# Simulation.net
KiCad netlist of a schematic drawn in EasyEDA
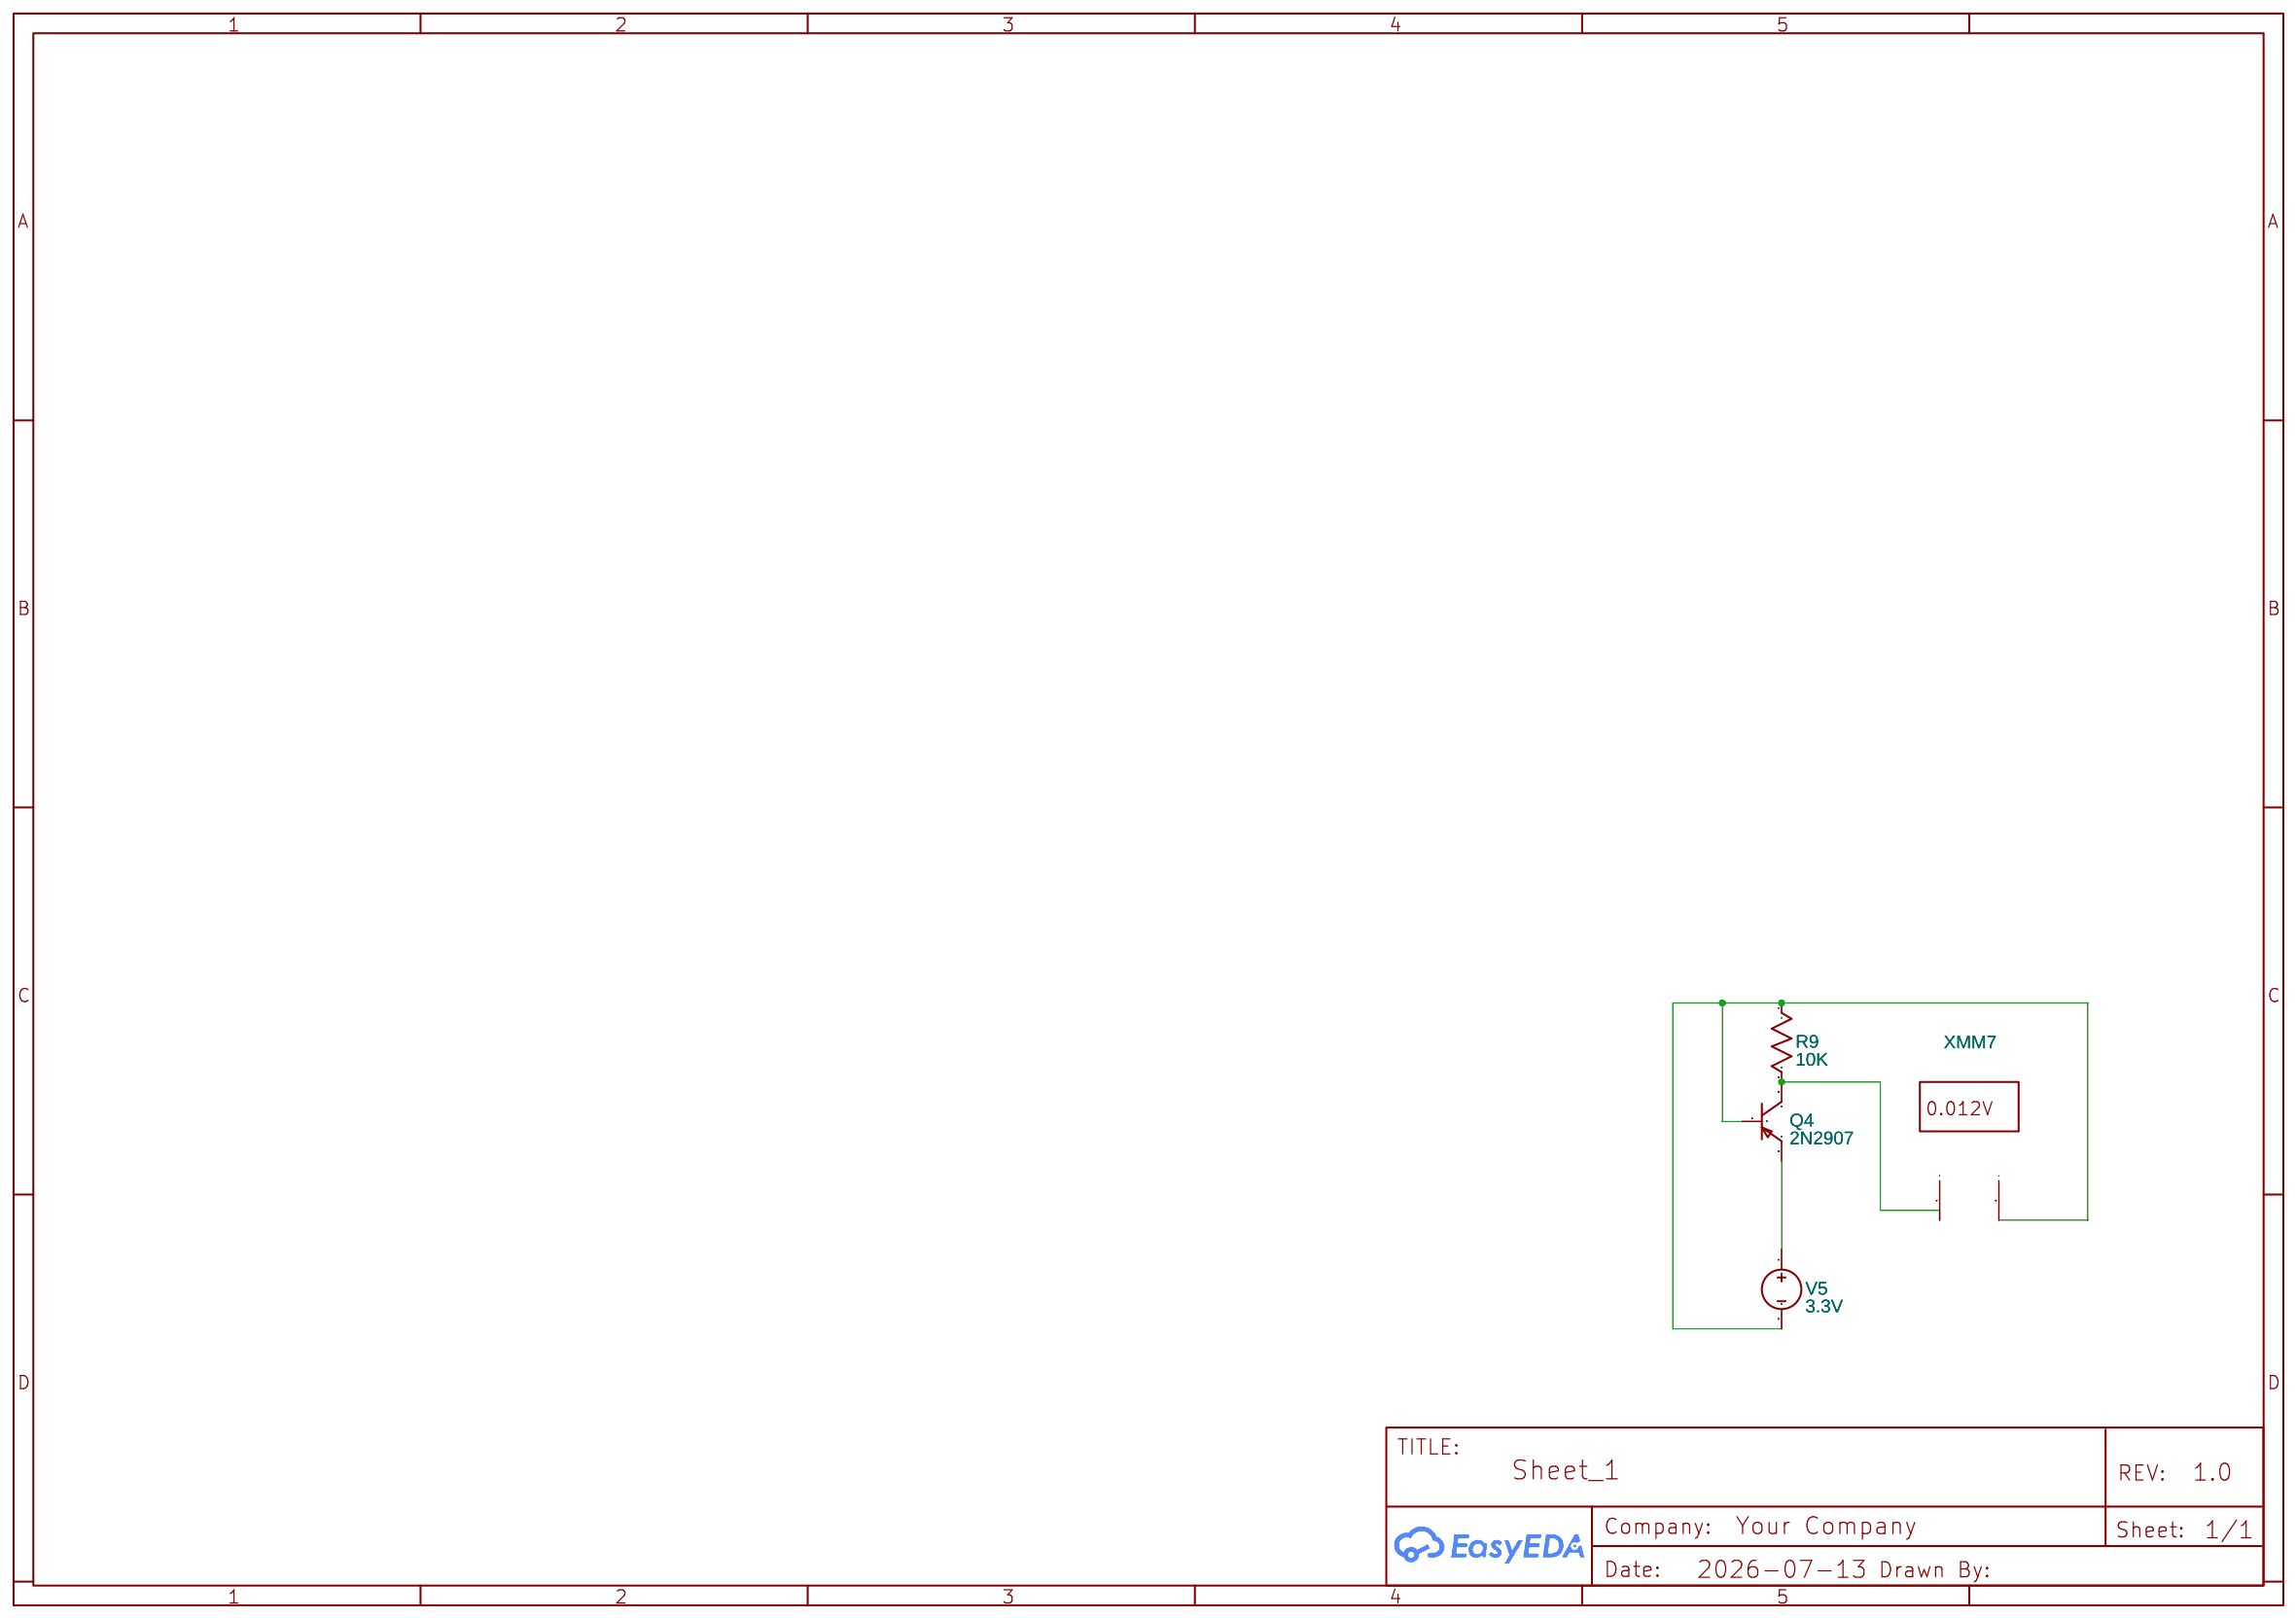
[diagram p0: schematic sheet]

(export (version "E")
  (design (tool "Eeschema 10.0.6"))
  (components
    (comp (ref "Q4") (value "2N2907") (libsource (lib "") (part "2N2907")))
    (comp (ref "R9") (value "10K") (libsource (lib "") (part "R_0603_US")))
    (comp (ref "V5") (value "3.3V") (libsource (lib "") (part "VDC")))
    (comp (ref "XMM7") (value "Multimeter") (libsource (lib "") (part "MULTIMETER")))
  )
  (nets
    (net (code "1") (name "Net-(Q4-B)") (class "Default")
      (node (ref "Q4") (pin "2") (pinfunction "B_2") (pintype "unspecified"))
      (node (ref "R9") (pin "1") (pinfunction "1_1") (pintype "unspecified"))
      (node (ref "V5") (pin "2") (pinfunction "2_2") (pintype "unspecified"))
      (node (ref "XMM7") (pin "2") (pinfunction "I_2") (pintype "unspecified"))
    )
    (net (code "2") (name "Net-(Q4-C)") (class "Default")
      (node (ref "Q4") (pin "1") (pinfunction "C_1") (pintype "unspecified"))
      (node (ref "R9") (pin "2") (pinfunction "2_2") (pintype "unspecified"))
      (node (ref "XMM7") (pin "1") (pinfunction "+_1") (pintype "unspecified"))
    )
    (net (code "3") (name "Net-(Q4-E)") (class "Default")
      (node (ref "Q4") (pin "3") (pinfunction "E_3") (pintype "unspecified"))
      (node (ref "V5") (pin "1") (pinfunction "1_1") (pintype "unspecified"))
    )
  )
)
